# ControlVCCLS.net
KiCad netlist of a schematic drawn in Altium Designer
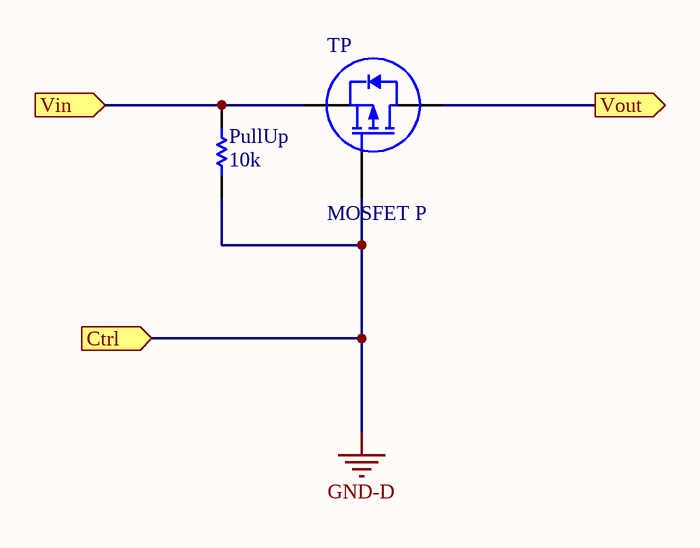
[diagram p0: ControlVCCLS.SchDoc]

(export (version "E")
  (design (tool "Eeschema 10.0.6"))
  (components
    (comp (ref "PullUp") (value "10k") (footprint "0805") (libsource (lib "LIBEBAL") (part "RES")))
    (comp (ref "TP") (value "MOSFET P") (footprint "SOT23") (libsource (lib "LIBEBAL") (part "MOSFET P")))
  )
  (nets
    (net (code "1") (name "/Vin") (class "Default")
      (node (ref "PullUp") (pin "2") (pinfunction "2_2") (pintype "passive"))
      (node (ref "TP") (pin "3") (pinfunction "S_3") (pintype "passive"))
    )
    (net (code "2") (name "/Vout") (class "Default")
      (node (ref "TP") (pin "2") (pinfunction "D_2") (pintype "passive"))
    )
    (net (code "3") (name "GND-D") (class "Default")
      (node (ref "PullUp") (pin "1") (pinfunction "1_1") (pintype "passive"))
      (node (ref "TP") (pin "1") (pinfunction "G_1") (pintype "passive"))
    )
  )
)
